# LogicBoard.net
KiCad netlist of a schematic drawn in EAGLE
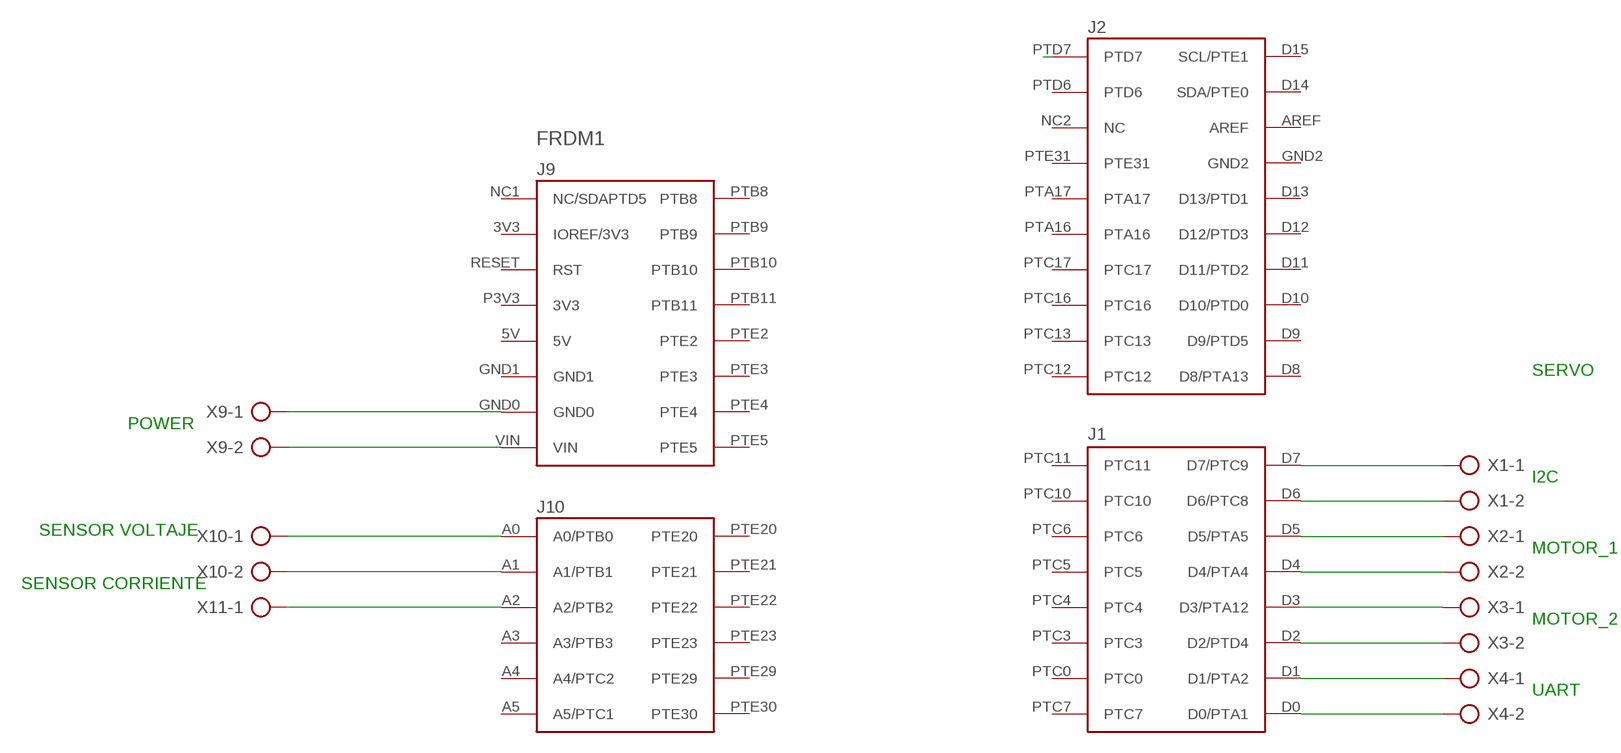
[diagram p0: schematic, sheet 1]

(export (version "E")
  (design (tool "Eeschema 10.0.6"))
  (components
    (comp (ref "FRDM1")
      (value "FRDM-KL25ZNORMAL")
      (footprint "eagle-import:FRDM_KL25Z_NORMAL")
      (fields (field (name "MF") "NXP USA") (field (name "MP") "FRDM-KL25Z"))
      (libsource (lib "eagle-import") (part "FRDM-KL25ZNORMAL"))
    )
    (comp (ref "X1")
      (value "AK500/2-H")
      (footprint "eagle-import:AK500_2-H")
      (libsource (lib "eagle-import") (part "AK500/2-H"))
    )
    (comp (ref "X2")
      (value "AK500/2-H")
      (footprint "eagle-import:AK500_2-H")
      (libsource (lib "eagle-import") (part "AK500/2-H"))
    )
    (comp (ref "X3")
      (value "AK500/2-H")
      (footprint "eagle-import:AK500_2-H")
      (libsource (lib "eagle-import") (part "AK500/2-H"))
    )
    (comp (ref "X4")
      (value "AK500/2-H")
      (footprint "eagle-import:AK500_2-H")
      (libsource (lib "eagle-import") (part "AK500/2-H"))
    )
    (comp (ref "X9")
      (value "AK500/2-H")
      (footprint "eagle-import:AK500_2-H")
      (libsource (lib "eagle-import") (part "AK500/2-H"))
    )
    (comp (ref "X10")
      (value "AK500/2-H")
      (footprint "eagle-import:AK500_2-H")
      (libsource (lib "eagle-import") (part "AK500/2-H"))
    )
    (comp (ref "X11")
      (value "AK500/2-H")
      (footprint "eagle-import:AK500_2-H")
      (libsource (lib "eagle-import") (part "AK500/2-H"))
    )
  )
  (nets
    (net (code "1") (name "Net-(FRDM1-A0{slash}PTB0)") (class "Default")
      (node (ref "FRDM1") (pin "A0") (pinfunction "A0/PTB0_A0") (pintype "bidirectional"))
      (node (ref "X10") (pin "1") (pinfunction "KL_1") (pintype "passive"))
    )
    (net (code "2") (name "Net-(FRDM1-A1{slash}PTB1)") (class "Default")
      (node (ref "FRDM1") (pin "A1") (pinfunction "A1/PTB1_A1") (pintype "bidirectional"))
      (node (ref "X10") (pin "2") (pinfunction "KL_2") (pintype "passive"))
    )
    (net (code "3") (name "Net-(FRDM1-A2{slash}PTB2)") (class "Default")
      (node (ref "FRDM1") (pin "A2") (pinfunction "A2/PTB2_A2") (pintype "bidirectional"))
      (node (ref "X11") (pin "1") (pinfunction "KL_1") (pintype "passive"))
    )
    (net (code "4") (name "Net-(FRDM1-D0{slash}PTA1)") (class "Default")
      (node (ref "FRDM1") (pin "D0") (pinfunction "D0/PTA1_D0") (pintype "bidirectional"))
      (node (ref "X4") (pin "2") (pinfunction "KL_2") (pintype "passive"))
    )
    (net (code "5") (name "Net-(FRDM1-D1{slash}PTA2)") (class "Default")
      (node (ref "FRDM1") (pin "D1") (pinfunction "D1/PTA2_D1") (pintype "bidirectional"))
      (node (ref "X4") (pin "1") (pinfunction "KL_1") (pintype "passive"))
    )
    (net (code "6") (name "Net-(FRDM1-D2{slash}PTD4)") (class "Default")
      (node (ref "FRDM1") (pin "D2") (pinfunction "D2/PTD4_D2") (pintype "bidirectional"))
      (node (ref "X3") (pin "2") (pinfunction "KL_2") (pintype "passive"))
    )
    (net (code "7") (name "Net-(FRDM1-D3{slash}PTA12)") (class "Default")
      (node (ref "FRDM1") (pin "D3") (pinfunction "D3/PTA12_D3") (pintype "bidirectional"))
      (node (ref "X3") (pin "1") (pinfunction "KL_1") (pintype "passive"))
    )
    (net (code "8") (name "Net-(FRDM1-D4{slash}PTA4)") (class "Default")
      (node (ref "FRDM1") (pin "D4") (pinfunction "D4/PTA4_D4") (pintype "bidirectional"))
      (node (ref "X2") (pin "2") (pinfunction "KL_2") (pintype "passive"))
    )
    (net (code "9") (name "Net-(FRDM1-D5{slash}PTA5)") (class "Default")
      (node (ref "FRDM1") (pin "D5") (pinfunction "D5/PTA5_D5") (pintype "bidirectional"))
      (node (ref "X2") (pin "1") (pinfunction "KL_1") (pintype "passive"))
    )
    (net (code "10") (name "Net-(FRDM1-D6{slash}PTC8)") (class "Default")
      (node (ref "FRDM1") (pin "D6") (pinfunction "D6/PTC8_D6") (pintype "bidirectional"))
      (node (ref "X1") (pin "2") (pinfunction "KL_2") (pintype "passive"))
    )
    (net (code "11") (name "Net-(FRDM1-D7{slash}PTC9)") (class "Default")
      (node (ref "FRDM1") (pin "D7") (pinfunction "D7/PTC9_D7") (pintype "bidirectional"))
      (node (ref "X1") (pin "1") (pinfunction "KL_1") (pintype "passive"))
    )
    (net (code "12") (name "Net-(X9A-KL)") (class "Default")
      (node (ref "FRDM1") (pin "GND0") (pinfunction "GND0_GND0") (pintype "bidirectional"))
      (node (ref "X9") (pin "1") (pinfunction "KL_1") (pintype "passive"))
    )
    (net (code "13") (name "Net-(X9B-KL)") (class "Default")
      (node (ref "FRDM1") (pin "VIN") (pinfunction "VIN_VIN") (pintype "bidirectional"))
      (node (ref "X9") (pin "2") (pinfunction "KL_2") (pintype "passive"))
    )
    (net (code "14") (name "unconnected-(FRDM1-3V3-PadP3V3)") (class "Default")
      (node (ref "FRDM1") (pin "P3V3") (pinfunction "3V3_P3V3") (pintype "bidirectional"))
    )
    (net (code "15") (name "unconnected-(FRDM1-A3{slash}PTB3-PadA3)") (class "Default")
      (node (ref "FRDM1") (pin "A3") (pinfunction "A3/PTB3_A3") (pintype "bidirectional"))
    )
    (net (code "16") (name "unconnected-(FRDM1-A4{slash}PTC2-PadA4)") (class "Default")
      (node (ref "FRDM1") (pin "A4") (pinfunction "A4/PTC2_A4") (pintype "bidirectional"))
    )
    (net (code "17") (name "unconnected-(FRDM1-A5{slash}PTC1-PadA5)") (class "Default")
      (node (ref "FRDM1") (pin "A5") (pinfunction "A5/PTC1_A5") (pintype "bidirectional"))
    )
    (net (code "18") (name "unconnected-(FRDM1-D8{slash}PTA13-PadD8)") (class "Default")
      (node (ref "FRDM1") (pin "D8") (pinfunction "D8/PTA13_D8") (pintype "bidirectional"))
    )
    (net (code "19") (name "unconnected-(FRDM1-D9{slash}PTD5-PadD9)") (class "Default")
      (node (ref "FRDM1") (pin "D9") (pinfunction "D9/PTD5_D9") (pintype "bidirectional"))
    )
    (net (code "20") (name "unconnected-(FRDM1-D10{slash}PTD0-PadD10)") (class "Default")
      (node (ref "FRDM1") (pin "D10") (pinfunction "D10/PTD0_D10") (pintype "bidirectional"))
    )
    (net (code "21") (name "unconnected-(FRDM1-D11{slash}PTD2-PadD11)") (class "Default")
      (node (ref "FRDM1") (pin "D11") (pinfunction "D11/PTD2_D11") (pintype "bidirectional"))
    )
    (net (code "22") (name "unconnected-(FRDM1-D12{slash}PTD3-PadD12)") (class "Default")
      (node (ref "FRDM1") (pin "D12") (pinfunction "D12/PTD3_D12") (pintype "bidirectional"))
    )
    (net (code "23") (name "unconnected-(FRDM1-D13{slash}PTD1-PadD13)") (class "Default")
      (node (ref "FRDM1") (pin "D13") (pinfunction "D13/PTD1_D13") (pintype "bidirectional"))
    )
    (net (code "24") (name "unconnected-(FRDM1-IOREF{slash}3V3-Pad3V3)") (class "Default")
      (node (ref "FRDM1") (pin "3V3") (pinfunction "IOREF/3V3_3V3") (pintype "bidirectional"))
    )
    (net (code "25") (name "unconnected-(FRDM1-NC-PadNC2)") (class "Default")
      (node (ref "FRDM1") (pin "NC2") (pinfunction "NC_NC2") (pintype "bidirectional"))
    )
    (net (code "26") (name "unconnected-(FRDM1-NC{slash}SDAPTD5-PadNC1)") (class "Default")
      (node (ref "FRDM1") (pin "NC1") (pinfunction "NC/SDAPTD5_NC1") (pintype "bidirectional"))
    )
    (net (code "27") (name "unconnected-(FRDM1-Pad5V)") (class "Default")
      (node (ref "FRDM1") (pin "5V") (pinfunction "5V_5V") (pintype "bidirectional"))
    )
    (net (code "28") (name "unconnected-(FRDM1-PadAREF)") (class "Default")
      (node (ref "FRDM1") (pin "AREF") (pinfunction "AREF_AREF") (pintype "bidirectional"))
    )
    (net (code "29") (name "unconnected-(FRDM1-PadGND1)") (class "Default")
      (node (ref "FRDM1") (pin "GND1") (pinfunction "GND1_GND1") (pintype "bidirectional"))
    )
    (net (code "30") (name "unconnected-(FRDM1-PadGND2)") (class "Default")
      (node (ref "FRDM1") (pin "GND2") (pinfunction "GND2_GND2") (pintype "bidirectional"))
    )
    (net (code "31") (name "unconnected-(FRDM1-PadPTA16)") (class "Default")
      (node (ref "FRDM1") (pin "PTA16") (pinfunction "PTA16_PTA16") (pintype "bidirectional"))
    )
    (net (code "32") (name "unconnected-(FRDM1-PadPTA17)") (class "Default")
      (node (ref "FRDM1") (pin "PTA17") (pinfunction "PTA17_PTA17") (pintype "bidirectional"))
    )
    (net (code "33") (name "unconnected-(FRDM1-PadPTB8)") (class "Default")
      (node (ref "FRDM1") (pin "PTB8") (pinfunction "PTB8_PTB8") (pintype "bidirectional"))
    )
    (net (code "34") (name "unconnected-(FRDM1-PadPTB9)") (class "Default")
      (node (ref "FRDM1") (pin "PTB9") (pinfunction "PTB9_PTB9") (pintype "bidirectional"))
    )
    (net (code "35") (name "unconnected-(FRDM1-PadPTB10)") (class "Default")
      (node (ref "FRDM1") (pin "PTB10") (pinfunction "PTB10_PTB10") (pintype "bidirectional"))
    )
    (net (code "36") (name "unconnected-(FRDM1-PadPTB11)") (class "Default")
      (node (ref "FRDM1") (pin "PTB11") (pinfunction "PTB11_PTB11") (pintype "bidirectional"))
    )
    (net (code "37") (name "unconnected-(FRDM1-PadPTC0)") (class "Default")
      (node (ref "FRDM1") (pin "PTC0") (pinfunction "PTC0_PTC0") (pintype "bidirectional"))
    )
    (net (code "38") (name "unconnected-(FRDM1-PadPTC3)") (class "Default")
      (node (ref "FRDM1") (pin "PTC3") (pinfunction "PTC3_PTC3") (pintype "bidirectional"))
    )
    (net (code "39") (name "unconnected-(FRDM1-PadPTC4)") (class "Default")
      (node (ref "FRDM1") (pin "PTC4") (pinfunction "PTC4_PTC4") (pintype "bidirectional"))
    )
    (net (code "40") (name "unconnected-(FRDM1-PadPTC5)") (class "Default")
      (node (ref "FRDM1") (pin "PTC5") (pinfunction "PTC5_PTC5") (pintype "bidirectional"))
    )
    (net (code "41") (name "unconnected-(FRDM1-PadPTC6)") (class "Default")
      (node (ref "FRDM1") (pin "PTC6") (pinfunction "PTC6_PTC6") (pintype "bidirectional"))
    )
    (net (code "42") (name "unconnected-(FRDM1-PadPTC7)") (class "Default")
      (node (ref "FRDM1") (pin "PTC7") (pinfunction "PTC7_PTC7") (pintype "bidirectional"))
    )
    (net (code "43") (name "unconnected-(FRDM1-PadPTC10)") (class "Default")
      (node (ref "FRDM1") (pin "PTC10") (pinfunction "PTC10_PTC10") (pintype "bidirectional"))
    )
    (net (code "44") (name "unconnected-(FRDM1-PadPTC11)") (class "Default")
      (node (ref "FRDM1") (pin "PTC11") (pinfunction "PTC11_PTC11") (pintype "bidirectional"))
    )
    (net (code "45") (name "unconnected-(FRDM1-PadPTC12)") (class "Default")
      (node (ref "FRDM1") (pin "PTC12") (pinfunction "PTC12_PTC12") (pintype "bidirectional"))
    )
    (net (code "46") (name "unconnected-(FRDM1-PadPTC13)") (class "Default")
      (node (ref "FRDM1") (pin "PTC13") (pinfunction "PTC13_PTC13") (pintype "bidirectional"))
    )
    (net (code "47") (name "unconnected-(FRDM1-PadPTC16)") (class "Default")
      (node (ref "FRDM1") (pin "PTC16") (pinfunction "PTC16_PTC16") (pintype "bidirectional"))
    )
    (net (code "48") (name "unconnected-(FRDM1-PadPTC17)") (class "Default")
      (node (ref "FRDM1") (pin "PTC17") (pinfunction "PTC17_PTC17") (pintype "bidirectional"))
    )
    (net (code "49") (name "unconnected-(FRDM1-PadPTD6)") (class "Default")
      (node (ref "FRDM1") (pin "PTD6") (pinfunction "PTD6_PTD6") (pintype "bidirectional"))
    )
    (net (code "50") (name "unconnected-(FRDM1-PadPTD7)") (class "Default")
      (node (ref "FRDM1") (pin "PTD7") (pinfunction "PTD7_PTD7") (pintype "bidirectional"))
    )
    (net (code "51") (name "unconnected-(FRDM1-PadPTE2)") (class "Default")
      (node (ref "FRDM1") (pin "PTE2") (pinfunction "PTE2_PTE2") (pintype "bidirectional"))
    )
    (net (code "52") (name "unconnected-(FRDM1-PadPTE3)") (class "Default")
      (node (ref "FRDM1") (pin "PTE3") (pinfunction "PTE3_PTE3") (pintype "bidirectional"))
    )
    (net (code "53") (name "unconnected-(FRDM1-PadPTE4)") (class "Default")
      (node (ref "FRDM1") (pin "PTE4") (pinfunction "PTE4_PTE4") (pintype "bidirectional"))
    )
    (net (code "54") (name "unconnected-(FRDM1-PadPTE5)") (class "Default")
      (node (ref "FRDM1") (pin "PTE5") (pinfunction "PTE5_PTE5") (pintype "bidirectional"))
    )
    (net (code "55") (name "unconnected-(FRDM1-PadPTE20)") (class "Default")
      (node (ref "FRDM1") (pin "PTE20") (pinfunction "PTE20_PTE20") (pintype "bidirectional"))
    )
    (net (code "56") (name "unconnected-(FRDM1-PadPTE21)") (class "Default")
      (node (ref "FRDM1") (pin "PTE21") (pinfunction "PTE21_PTE21") (pintype "bidirectional"))
    )
    (net (code "57") (name "unconnected-(FRDM1-PadPTE22)") (class "Default")
      (node (ref "FRDM1") (pin "PTE22") (pinfunction "PTE22_PTE22") (pintype "bidirectional"))
    )
    (net (code "58") (name "unconnected-(FRDM1-PadPTE23)") (class "Default")
      (node (ref "FRDM1") (pin "PTE23") (pinfunction "PTE23_PTE23") (pintype "bidirectional"))
    )
    (net (code "59") (name "unconnected-(FRDM1-PadPTE29)") (class "Default")
      (node (ref "FRDM1") (pin "PTE29") (pinfunction "PTE29_PTE29") (pintype "bidirectional"))
    )
    (net (code "60") (name "unconnected-(FRDM1-PadPTE30)") (class "Default")
      (node (ref "FRDM1") (pin "PTE30") (pinfunction "PTE30_PTE30") (pintype "bidirectional"))
    )
    (net (code "61") (name "unconnected-(FRDM1-PadPTE31)") (class "Default")
      (node (ref "FRDM1") (pin "PTE31") (pinfunction "PTE31_PTE31") (pintype "bidirectional"))
    )
    (net (code "62") (name "unconnected-(FRDM1-RST-PadRESET)") (class "Default")
      (node (ref "FRDM1") (pin "RESET") (pinfunction "RST_RESET") (pintype "bidirectional"))
    )
    (net (code "63") (name "unconnected-(FRDM1-SCL{slash}PTE1-PadD15)") (class "Default")
      (node (ref "FRDM1") (pin "D15") (pinfunction "SCL/PTE1_D15") (pintype "bidirectional"))
    )
    (net (code "64") (name "unconnected-(FRDM1-SDA{slash}PTE0-PadD14)") (class "Default")
      (node (ref "FRDM1") (pin "D14") (pinfunction "SDA/PTE0_D14") (pintype "bidirectional"))
    )
  )
)
